# Mixer-Analog-OPA2134-Rev-I.net
KiCad netlist of a schematic drawn in EAGLE
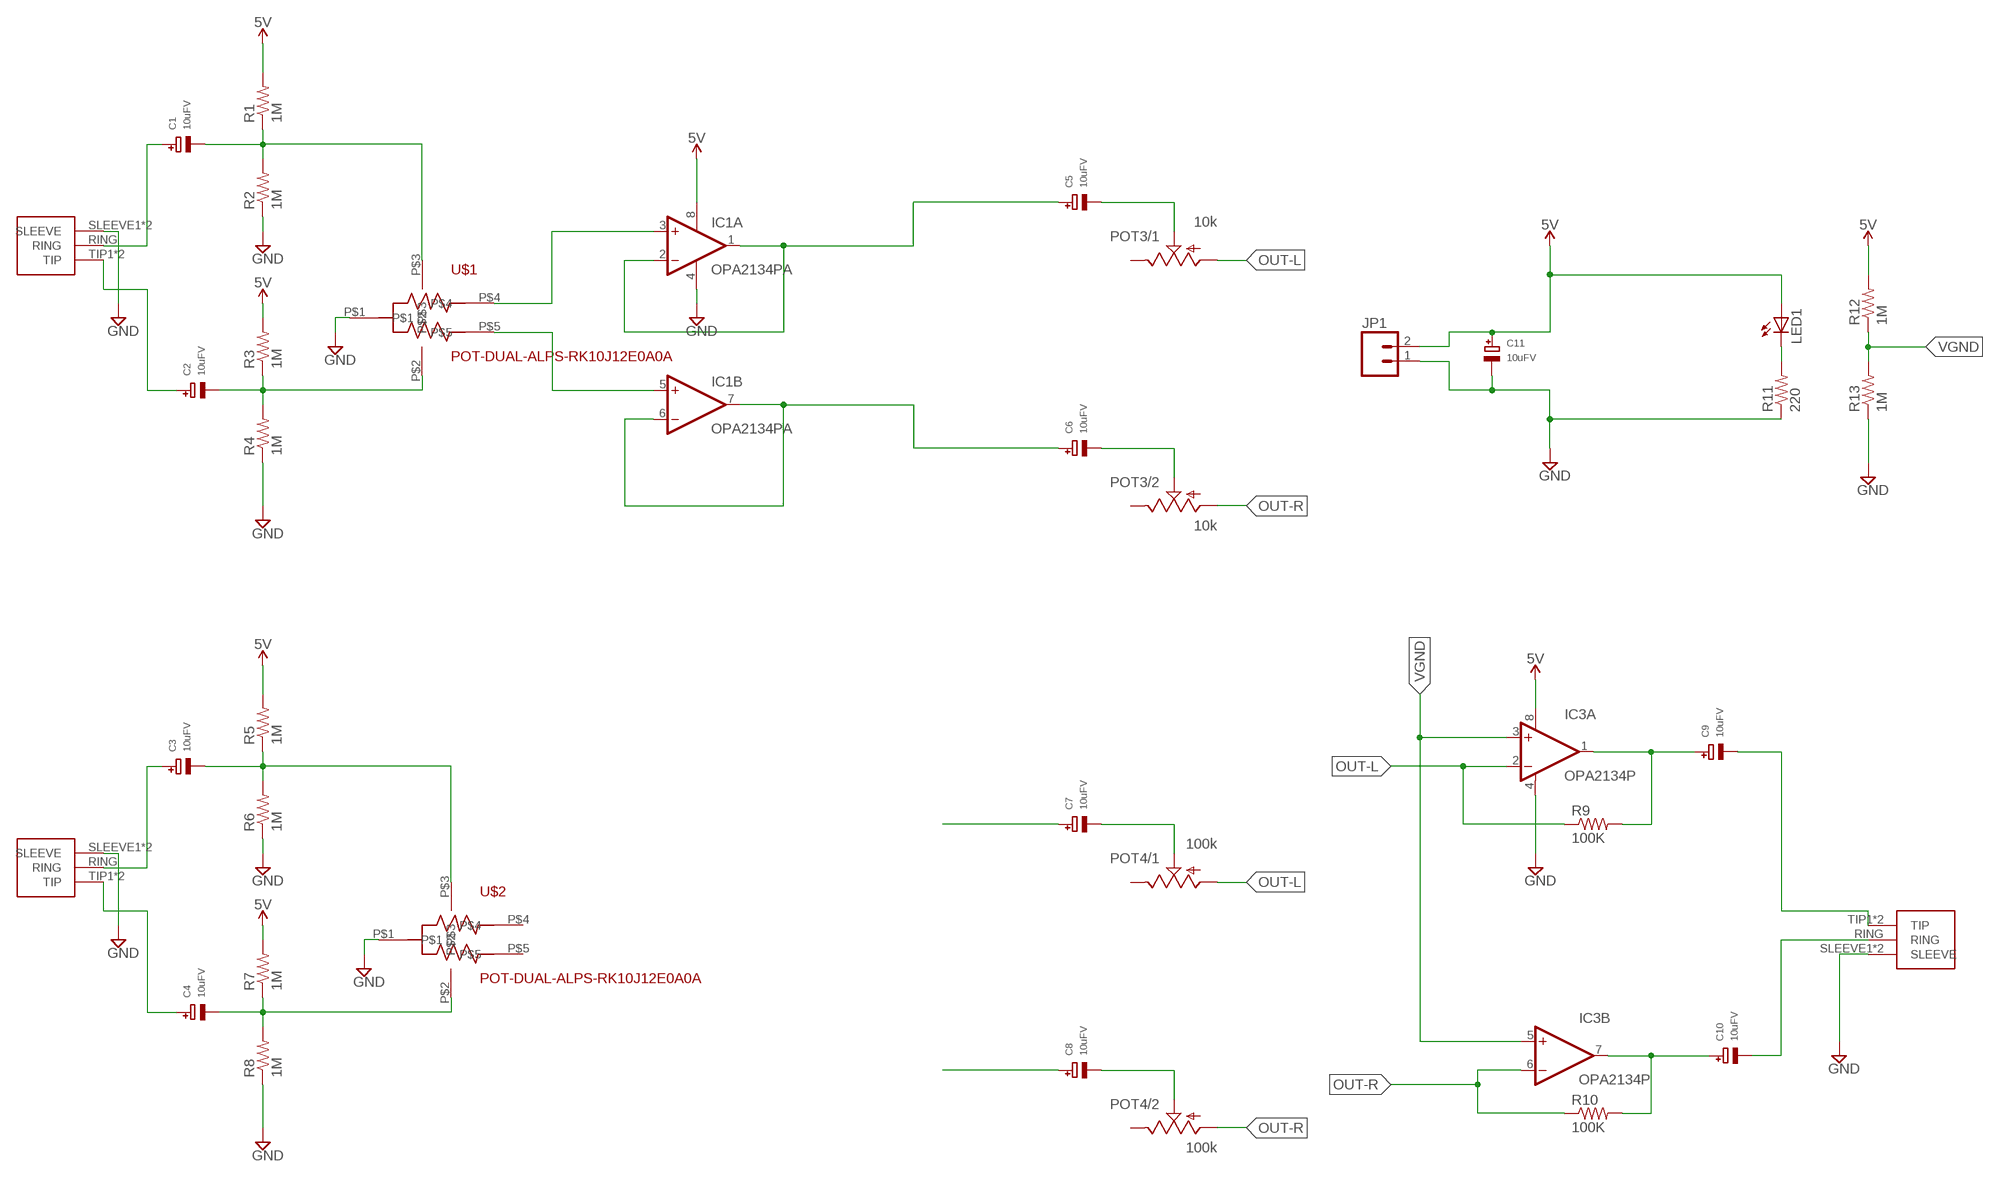
[diagram p0: schematic, sheet 1]

(export (version "E")
  (design (tool "Eeschema 10.0.6"))
  (components
    (comp (ref "C1")
      (value "10uFV")
      (footprint "eagle-import:CELEC_3.5MM_8MM")
      (libsource (lib "eagle-import") (part "CAP_ELECTROLYTICPTH_3.5MMGRID_8MMDIA"))
    )
    (comp (ref "C2")
      (value "10uFV")
      (footprint "eagle-import:CELEC_3.5MM_8MM")
      (libsource (lib "eagle-import") (part "CAP_ELECTROLYTICPTH_3.5MMGRID_8MMDIA"))
    )
    (comp (ref "C3")
      (value "10uFV")
      (footprint "eagle-import:CELEC_3.5MM_8MM")
      (libsource (lib "eagle-import") (part "CAP_ELECTROLYTICPTH_3.5MMGRID_8MMDIA"))
    )
    (comp (ref "C4")
      (value "10uFV")
      (footprint "eagle-import:CELEC_3.5MM_8MM")
      (libsource (lib "eagle-import") (part "CAP_ELECTROLYTICPTH_3.5MMGRID_8MMDIA"))
    )
    (comp (ref "C5")
      (value "10uFV")
      (footprint "eagle-import:CELEC_3.5MM_8MM")
      (libsource (lib "eagle-import") (part "CAP_ELECTROLYTICPTH_3.5MMGRID_8MMDIA"))
    )
    (comp (ref "C6")
      (value "10uFV")
      (footprint "eagle-import:CELEC_3.5MM_8MM")
      (libsource (lib "eagle-import") (part "CAP_ELECTROLYTICPTH_3.5MMGRID_8MMDIA"))
    )
    (comp (ref "C7")
      (value "10uFV")
      (footprint "eagle-import:CELEC_3.5MM_8MM")
      (libsource (lib "eagle-import") (part "CAP_ELECTROLYTICPTH_3.5MMGRID_8MMDIA"))
    )
    (comp (ref "C8")
      (value "10uFV")
      (footprint "eagle-import:CELEC_3.5MM_8MM")
      (libsource (lib "eagle-import") (part "CAP_ELECTROLYTICPTH_3.5MMGRID_8MMDIA"))
    )
    (comp (ref "C9")
      (value "10uFV")
      (footprint "eagle-import:CELEC_3.5MM_8MM")
      (libsource (lib "eagle-import") (part "CAP_ELECTROLYTICPTH_3.5MMGRID_8MMDIA"))
    )
    (comp (ref "C10")
      (value "10uFV")
      (footprint "eagle-import:CELEC_3.5MM_8MM")
      (libsource (lib "eagle-import") (part "CAP_ELECTROLYTICPTH_3.5MMGRID_8MMDIA"))
    )
    (comp (ref "C11")
      (value "10uFV")
      (footprint "eagle-import:CELEC_3.5MM_8MM")
      (libsource (lib "eagle-import") (part "CAP_ELECTROLYTICPTH_3.5MMGRID_8MMDIA"))
    )
    (comp (ref "IC1")
      (value "OPA2134PA")
      (footprint "eagle-import:DIL08")
      (libsource (lib "eagle-import") (part "OPA2PA134"))
    )
    (comp (ref "IC3")
      (value "OPA2134P")
      (footprint "eagle-import:DIL08")
      (fields (field (name "MF") "TEXAS INSTRUMENTS") (field (name "MPN") "OPA2134PA"))
      (libsource (lib "eagle-import") (part "OPA2134P"))
    )
    (comp (ref "J1")
      (value "1/8\"-F-STEREO-PCB")
      (footprint "eagle-import:1_8_-F-STEREO-PCB")
      (libsource (lib "eagle-import") (part "1/8{dblquote}-F-STEREO-PCB"))
    )
    (comp (ref "J2")
      (value "1/8\"-F-STEREO-PCB")
      (footprint "eagle-import:1_8_-F-STEREO-PCB")
      (libsource (lib "eagle-import") (part "1/8{dblquote}-F-STEREO-PCB"))
    )
    (comp (ref "J3")
      (value "1/8\"-F-STEREO-PCB")
      (footprint "eagle-import:1_8_-F-STEREO-PCB")
      (libsource (lib "eagle-import") (part "1/8{dblquote}-F-STEREO-PCB"))
    )
    (comp (ref "JP1")
      (value "M02LOCK")
      (footprint "eagle-import:1X02_LOCK")
      (libsource (lib "eagle-import") (part "M02LOCK"))
    )
    (comp (ref "LED1")
      (value "LED3MM")
      (footprint "eagle-import:LED3MM")
      (libsource (lib "eagle-import") (part "LED3MM"))
    )
    (comp (ref "POT3")
      (value "10k")
      (footprint "eagle-import:PTV112")
      (fields
        (field (name "MF") "STMicroelectronics")
        (field (name "MP") "PTV112")
        (field (name "SPICEPREFIX") "J")
      )
      (libsource (lib "eagle-import") (part "POT-DUAL-PTV112-4420"))
    )
    (comp (ref "POT4")
      (value "100k")
      (footprint "eagle-import:PTV112")
      (fields
        (field (name "MF") "STMicroelectronics")
        (field (name "MP") "PTV112")
        (field (name "SPICEPREFIX") "J")
      )
      (libsource (lib "eagle-import") (part "POT-DUAL-PTV112-4420"))
    )
    (comp (ref "R1")
      (value "1M")
      (footprint "eagle-import:AXIAL-0.3EZ")
      (fields (field (name "SPICEPREFIX") "R"))
      (libsource (lib "eagle-import") (part "RESISTOREZ"))
    )
    (comp (ref "R2")
      (value "1M")
      (footprint "eagle-import:AXIAL-0.3")
      (fields (field (name "SPICEPREFIX") "R"))
      (libsource (lib "eagle-import") (part "RESISTORAXIAL-0.3"))
    )
    (comp (ref "R3")
      (value "1M")
      (footprint "eagle-import:AXIAL-0.3EZ")
      (fields (field (name "SPICEPREFIX") "R"))
      (libsource (lib "eagle-import") (part "RESISTOREZ"))
    )
    (comp (ref "R4")
      (value "1M")
      (footprint "eagle-import:AXIAL-0.3EZ")
      (fields (field (name "SPICEPREFIX") "R"))
      (libsource (lib "eagle-import") (part "RESISTOREZ"))
    )
    (comp (ref "R5")
      (value "1M")
      (footprint "eagle-import:AXIAL-0.3EZ")
      (fields (field (name "SPICEPREFIX") "R"))
      (libsource (lib "eagle-import") (part "RESISTOREZ"))
    )
    (comp (ref "R6")
      (value "1M")
      (footprint "eagle-import:AXIAL-0.3EZ")
      (fields (field (name "SPICEPREFIX") "R"))
      (libsource (lib "eagle-import") (part "RESISTOREZ"))
    )
    (comp (ref "R7")
      (value "1M")
      (footprint "eagle-import:AXIAL-0.3EZ")
      (fields (field (name "SPICEPREFIX") "R"))
      (libsource (lib "eagle-import") (part "RESISTOREZ"))
    )
    (comp (ref "R8")
      (value "1M")
      (footprint "eagle-import:AXIAL-0.3EZ")
      (fields (field (name "SPICEPREFIX") "R"))
      (libsource (lib "eagle-import") (part "RESISTOREZ"))
    )
    (comp (ref "R9")
      (value "100K")
      (footprint "eagle-import:AXIAL-0.3EZ")
      (fields (field (name "SPICEPREFIX") "R"))
      (libsource (lib "eagle-import") (part "RESISTOREZ"))
    )
    (comp (ref "R10")
      (value "100K")
      (footprint "eagle-import:AXIAL-0.3EZ")
      (fields (field (name "SPICEPREFIX") "R"))
      (libsource (lib "eagle-import") (part "RESISTOREZ"))
    )
    (comp (ref "R11")
      (value "220")
      (footprint "eagle-import:AXIAL-0.3EZ")
      (libsource (lib "eagle-import") (part "RESISTOREZ"))
    )
    (comp (ref "R12")
      (value "1M")
      (footprint "eagle-import:AXIAL-0.3EZ")
      (libsource (lib "eagle-import") (part "RESISTOREZ"))
    )
    (comp (ref "R13")
      (value "1M")
      (footprint "eagle-import:AXIAL-0.3EZ")
      (libsource (lib "eagle-import") (part "RESISTOREZ"))
    )
    (comp (ref "U$1")
      (value "POT-DUAL-ALPS-RK10J12E0A0A")
      (footprint "eagle-import:POT-DUAL-ALPS-RK10J12E0A0A")
      (libsource (lib "eagle-import") (part "POT-DUAL-ALPS-RK10J12E0A0A"))
    )
    (comp (ref "U$2")
      (value "POT-DUAL-ALPS-RK10J12E0A0A")
      (footprint "eagle-import:POT-DUAL-ALPS-RK10J12E0A0A")
      (libsource (lib "eagle-import") (part "POT-DUAL-ALPS-RK10J12E0A0A"))
    )
  )
  (nets
    (net (code "1") (name "5V") (class "Default")
      (node (ref "C11") (pin "+") (pinfunction "+_+") (pintype "passive"))
      (node (ref "IC1") (pin "8") (pinfunction "V+_8") (pintype "power_in"))
      (node (ref "IC3") (pin "8") (pinfunction "V+_8") (pintype "power_in"))
      (node (ref "JP1") (pin "2") (pinfunction "2_2") (pintype "passive"))
      (node (ref "LED1") (pin "A") (pinfunction "A_A") (pintype "passive"))
      (node (ref "R1") (pin "P$2") (pinfunction "2_P$2") (pintype "passive"))
      (node (ref "R12") (pin "P$2") (pinfunction "2_P$2") (pintype "passive"))
      (node (ref "R3") (pin "P$2") (pinfunction "2_P$2") (pintype "passive"))
      (node (ref "R5") (pin "P$2") (pinfunction "2_P$2") (pintype "passive"))
      (node (ref "R7") (pin "P$2") (pinfunction "2_P$2") (pintype "passive"))
    )
    (net (code "2") (name "GND") (class "Default")
      (node (ref "C11") (pin "-") (pinfunction "-_-") (pintype "passive"))
      (node (ref "IC1") (pin "4") (pinfunction "V-_4") (pintype "power_in"))
      (node (ref "IC3") (pin "4") (pinfunction "V-_4") (pintype "power_in"))
      (node (ref "J1") (pin "SLEEVE1") (pinfunction "SLEEVE_SLEEVE1") (pintype "bidirectional"))
      (node (ref "J1") (pin "SLEEVE2") (pinfunction "SLEEVE_SLEEVE2") (pintype "bidirectional"))
      (node (ref "J2") (pin "SLEEVE1") (pinfunction "SLEEVE_SLEEVE1") (pintype "bidirectional"))
      (node (ref "J2") (pin "SLEEVE2") (pinfunction "SLEEVE_SLEEVE2") (pintype "bidirectional"))
      (node (ref "J3") (pin "SLEEVE1") (pinfunction "SLEEVE_SLEEVE1") (pintype "bidirectional"))
      (node (ref "J3") (pin "SLEEVE2") (pinfunction "SLEEVE_SLEEVE2") (pintype "bidirectional"))
      (node (ref "JP1") (pin "1") (pinfunction "1_1") (pintype "passive"))
      (node (ref "R11") (pin "P$1") (pinfunction "1_P$1") (pintype "passive"))
      (node (ref "R13") (pin "P$1") (pinfunction "1_P$1") (pintype "passive"))
      (node (ref "R2") (pin "P$1") (pinfunction "1_P$1") (pintype "passive"))
      (node (ref "R4") (pin "P$1") (pinfunction "1_P$1") (pintype "passive"))
      (node (ref "R6") (pin "P$1") (pinfunction "1_P$1") (pintype "passive"))
      (node (ref "R8") (pin "P$1") (pinfunction "1_P$1") (pintype "passive"))
      (node (ref "U$1") (pin "P$1") (pinfunction "P$1_P$1") (pintype "bidirectional"))
      (node (ref "U$2") (pin "P$1") (pinfunction "P$1_P$1") (pintype "bidirectional"))
    )
    (net (code "3") (name "Net-(C1-Pad+)") (class "Default")
      (node (ref "C1") (pin "+") (pinfunction "+_+") (pintype "passive"))
      (node (ref "J1") (pin "RING") (pinfunction "RING_RING") (pintype "bidirectional"))
    )
    (net (code "4") (name "Net-(C2-Pad+)") (class "Default")
      (node (ref "C2") (pin "+") (pinfunction "+_+") (pintype "passive"))
      (node (ref "J1") (pin "TIP1") (pinfunction "TIP_TIP1") (pintype "bidirectional"))
      (node (ref "J1") (pin "TIP2") (pinfunction "TIP_TIP2") (pintype "bidirectional"))
    )
    (net (code "5") (name "Net-(C3-Pad+)") (class "Default")
      (node (ref "C3") (pin "+") (pinfunction "+_+") (pintype "passive"))
      (node (ref "J2") (pin "RING") (pinfunction "RING_RING") (pintype "bidirectional"))
    )
    (net (code "6") (name "Net-(C4-Pad+)") (class "Default")
      (node (ref "C4") (pin "+") (pinfunction "+_+") (pintype "passive"))
      (node (ref "J2") (pin "TIP1") (pinfunction "TIP_TIP1") (pintype "bidirectional"))
      (node (ref "J2") (pin "TIP2") (pinfunction "TIP_TIP2") (pintype "bidirectional"))
    )
    (net (code "7") (name "Net-(C9-Pad-)") (class "Default")
      (node (ref "C9") (pin "-") (pinfunction "-_-") (pintype "passive"))
      (node (ref "J3") (pin "TIP1") (pinfunction "TIP_TIP1") (pintype "bidirectional"))
      (node (ref "J3") (pin "TIP2") (pinfunction "TIP_TIP2") (pintype "bidirectional"))
    )
    (net (code "8") (name "Net-(C10-Pad-)") (class "Default")
      (node (ref "C10") (pin "-") (pinfunction "-_-") (pintype "passive"))
      (node (ref "J3") (pin "RING") (pinfunction "RING_RING") (pintype "bidirectional"))
    )
    (net (code "9") (name "Net-(IC1A-+IN)") (class "Default")
      (node (ref "IC1") (pin "3") (pinfunction "+IN_3") (pintype "input"))
      (node (ref "U$1") (pin "P$4") (pinfunction "P$4_P$4") (pintype "bidirectional"))
    )
    (net (code "10") (name "Net-(IC1A--IN)") (class "Default")
      (node (ref "C5") (pin "+") (pinfunction "+_+") (pintype "passive"))
      (node (ref "IC1") (pin "1") (pinfunction "OUT_1") (pintype "output"))
      (node (ref "IC1") (pin "2") (pinfunction "-IN_2") (pintype "input"))
    )
    (net (code "11") (name "Net-(IC1B-+IN)") (class "Default")
      (node (ref "IC1") (pin "5") (pinfunction "+IN_5") (pintype "input"))
      (node (ref "U$1") (pin "P$5") (pinfunction "P$5_P$5") (pintype "bidirectional"))
    )
    (net (code "12") (name "Net-(IC1B--IN)") (class "Default")
      (node (ref "C6") (pin "+") (pinfunction "+_+") (pintype "passive"))
      (node (ref "IC1") (pin "6") (pinfunction "-IN_6") (pintype "input"))
      (node (ref "IC1") (pin "7") (pinfunction "OUT_7") (pintype "output"))
    )
    (net (code "13") (name "Net-(IC3A-OUT)") (class "Default")
      (node (ref "C9") (pin "+") (pinfunction "+_+") (pintype "passive"))
      (node (ref "IC3") (pin "1") (pinfunction "OUT_1") (pintype "output"))
      (node (ref "R9") (pin "P$2") (pinfunction "2_P$2") (pintype "passive"))
    )
    (net (code "14") (name "Net-(IC3B-OUT)") (class "Default")
      (node (ref "C10") (pin "+") (pinfunction "+_+") (pintype "passive"))
      (node (ref "IC3") (pin "7") (pinfunction "OUT_7") (pintype "output"))
      (node (ref "R10") (pin "P$2") (pinfunction "2_P$2") (pintype "passive"))
    )
    (net (code "15") (name "Net-(LED1-C)") (class "Default")
      (node (ref "LED1") (pin "K") (pinfunction "C_K") (pintype "passive"))
      (node (ref "R11") (pin "P$2") (pinfunction "2_P$2") (pintype "passive"))
    )
    (net (code "16") (name "Net-(POT3A-S)") (class "Default")
      (node (ref "C5") (pin "-") (pinfunction "-_-") (pintype "passive"))
      (node (ref "POT3") (pin "1.2") (pinfunction "S_1.2") (pintype "passive"))
    )
    (net (code "17") (name "Net-(POT3B-S)") (class "Default")
      (node (ref "C6") (pin "-") (pinfunction "-_-") (pintype "passive"))
      (node (ref "POT3") (pin "2.2") (pinfunction "S_2.2") (pintype "passive"))
    )
    (net (code "18") (name "Net-(POT4A-S)") (class "Default")
      (node (ref "C7") (pin "-") (pinfunction "-_-") (pintype "passive"))
      (node (ref "POT4") (pin "1.2") (pinfunction "S_1.2") (pintype "passive"))
    )
    (net (code "19") (name "Net-(POT4B-S)") (class "Default")
      (node (ref "C8") (pin "-") (pinfunction "-_-") (pintype "passive"))
      (node (ref "POT4") (pin "2.2") (pinfunction "S_2.2") (pintype "passive"))
    )
    (net (code "20") (name "Net-(R1-1)") (class "Default")
      (node (ref "C1") (pin "-") (pinfunction "-_-") (pintype "passive"))
      (node (ref "R1") (pin "P$1") (pinfunction "1_P$1") (pintype "passive"))
      (node (ref "R2") (pin "P$2") (pinfunction "2_P$2") (pintype "passive"))
      (node (ref "U$1") (pin "P$3") (pinfunction "P$3_P$3") (pintype "bidirectional"))
    )
    (net (code "21") (name "Net-(R3-1)") (class "Default")
      (node (ref "C2") (pin "-") (pinfunction "-_-") (pintype "passive"))
      (node (ref "R3") (pin "P$1") (pinfunction "1_P$1") (pintype "passive"))
      (node (ref "R4") (pin "P$2") (pinfunction "2_P$2") (pintype "passive"))
      (node (ref "U$1") (pin "P$2") (pinfunction "P$2_P$2") (pintype "bidirectional"))
    )
    (net (code "22") (name "Net-(R5-1)") (class "Default")
      (node (ref "C3") (pin "-") (pinfunction "-_-") (pintype "passive"))
      (node (ref "R5") (pin "P$1") (pinfunction "1_P$1") (pintype "passive"))
      (node (ref "R6") (pin "P$2") (pinfunction "2_P$2") (pintype "passive"))
      (node (ref "U$2") (pin "P$3") (pinfunction "P$3_P$3") (pintype "bidirectional"))
    )
    (net (code "23") (name "Net-(R7-1)") (class "Default")
      (node (ref "C4") (pin "-") (pinfunction "-_-") (pintype "passive"))
      (node (ref "R7") (pin "P$1") (pinfunction "1_P$1") (pintype "passive"))
      (node (ref "R8") (pin "P$2") (pinfunction "2_P$2") (pintype "passive"))
      (node (ref "U$2") (pin "P$2") (pinfunction "P$2_P$2") (pintype "bidirectional"))
    )
    (net (code "24") (name "OUT-L") (class "Default")
      (node (ref "IC3") (pin "2") (pinfunction "-IN_2") (pintype "input"))
      (node (ref "POT3") (pin "1.1") (pinfunction "A_1.1") (pintype "passive"))
      (node (ref "POT4") (pin "1.1") (pinfunction "A_1.1") (pintype "passive"))
      (node (ref "R9") (pin "P$1") (pinfunction "1_P$1") (pintype "passive"))
    )
    (net (code "25") (name "OUT-R") (class "Default")
      (node (ref "IC3") (pin "6") (pinfunction "-IN_6") (pintype "input"))
      (node (ref "POT3") (pin "2.1") (pinfunction "A_2.1") (pintype "passive"))
      (node (ref "POT4") (pin "2.1") (pinfunction "A_2.1") (pintype "passive"))
      (node (ref "R10") (pin "P$1") (pinfunction "1_P$1") (pintype "passive"))
    )
    (net (code "26") (name "VGND") (class "Default")
      (node (ref "IC3") (pin "3") (pinfunction "+IN_3") (pintype "input"))
      (node (ref "IC3") (pin "5") (pinfunction "+IN_5") (pintype "input"))
      (node (ref "R12") (pin "P$1") (pinfunction "1_P$1") (pintype "passive"))
      (node (ref "R13") (pin "P$2") (pinfunction "2_P$2") (pintype "passive"))
    )
    (net (code "27") (name "unconnected-(C7-Pad+)") (class "Default")
      (node (ref "C7") (pin "+") (pinfunction "+_+") (pintype "passive"))
    )
    (net (code "28") (name "unconnected-(C8-Pad+)") (class "Default")
      (node (ref "C8") (pin "+") (pinfunction "+_+") (pintype "passive"))
    )
    (net (code "29") (name "unconnected-(POT3A-E-Pad1.3)") (class "Default")
      (node (ref "POT3") (pin "1.3") (pinfunction "E_1.3") (pintype "passive"))
    )
    (net (code "30") (name "unconnected-(POT3B-E-Pad2.3)") (class "Default")
      (node (ref "POT3") (pin "2.3") (pinfunction "E_2.3") (pintype "passive"))
    )
    (net (code "31") (name "unconnected-(POT4A-E-Pad1.3)") (class "Default")
      (node (ref "POT4") (pin "1.3") (pinfunction "E_1.3") (pintype "passive"))
    )
    (net (code "32") (name "unconnected-(POT4B-E-Pad2.3)") (class "Default")
      (node (ref "POT4") (pin "2.3") (pinfunction "E_2.3") (pintype "passive"))
    )
    (net (code "33") (name "unconnected-(U$2-PadP$4)") (class "Default")
      (node (ref "U$2") (pin "P$4") (pinfunction "P$4_P$4") (pintype "bidirectional"))
    )
    (net (code "34") (name "unconnected-(U$2-PadP$5)") (class "Default")
      (node (ref "U$2") (pin "P$5") (pinfunction "P$5_P$5") (pintype "bidirectional"))
    )
  )
)
